# new_v1.net
KiCad netlist of a schematic drawn in EAGLE
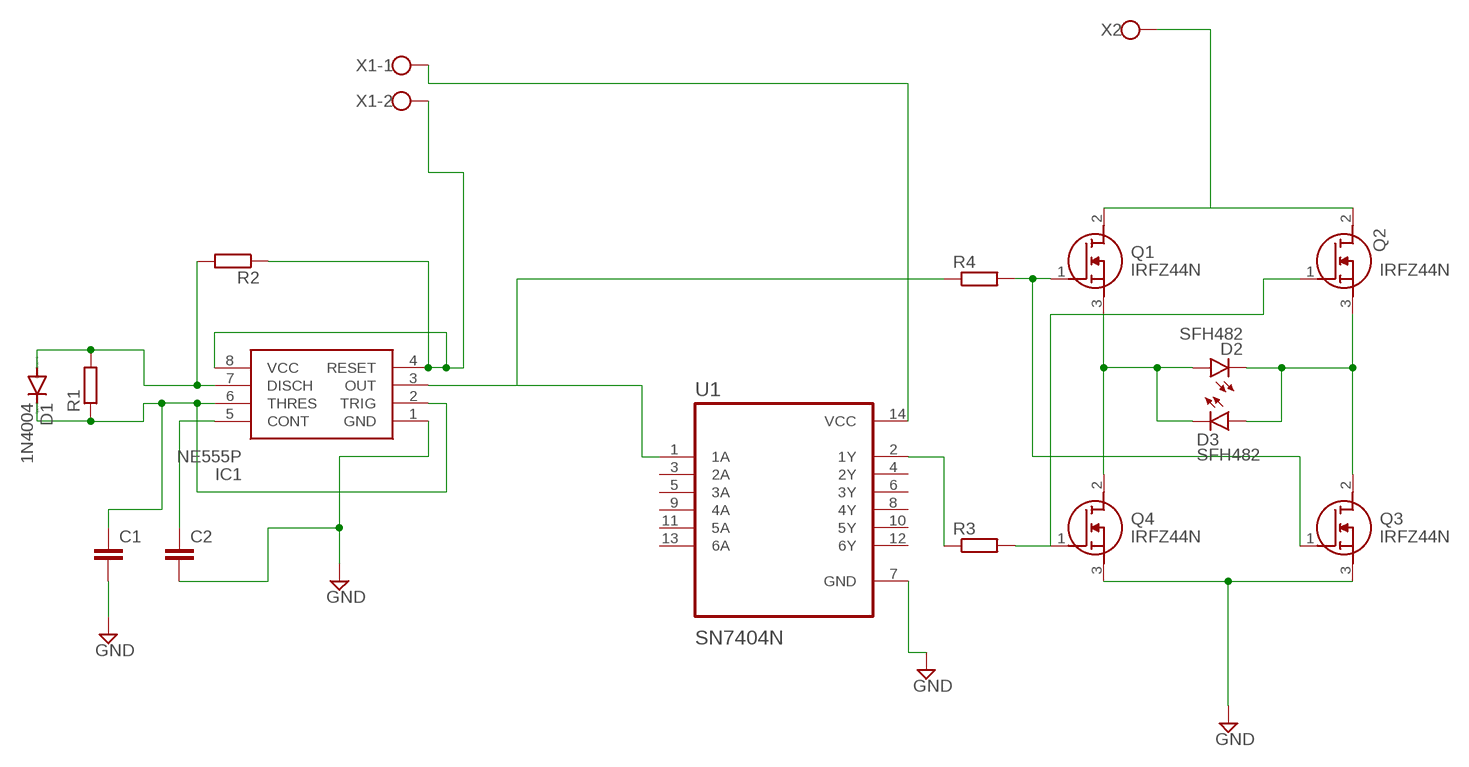
[diagram p0: schematic, sheet 1]

(export (version "E")
  (design (tool "Eeschema 10.0.6"))
  (components
    (comp (ref "C1")
      (value "C-EU025-030X050")
      (footprint "eagle-import:C025-030X050")
      (libsource (lib "eagle-import") (part "C-EU025-030X050"))
    )
    (comp (ref "C2")
      (value "C-EU025-030X050")
      (footprint "eagle-import:C025-030X050")
      (libsource (lib "eagle-import") (part "C-EU025-030X050"))
    )
    (comp (ref "D1")
      (value "1N4004")
      (footprint "eagle-import:DO41-10")
      (libsource (lib "eagle-import") (part "1N4004"))
    )
    (comp (ref "D2")
      (value "SFH482")
      (footprint "eagle-import:SFH482")
      (libsource (lib "eagle-import") (part "SFH482"))
    )
    (comp (ref "D3")
      (value "SFH482")
      (footprint "eagle-import:SFH482")
      (libsource (lib "eagle-import") (part "SFH482"))
    )
    (comp (ref "IC1")
      (value "NE555P")
      (footprint "eagle-import:DIP794W53P254L959H508Q8N")
      (fields (field (name "MOUSER_PART_NUMBER") "595-NE555P"))
      (libsource (lib "eagle-import") (part "NE555P"))
    )
    (comp (ref "Q1")
      (value "IRFZ44N")
      (footprint "eagle-import:TO254P440X1000X1900-3P")
      (libsource (lib "eagle-import") (part "IRFZ44N"))
    )
    (comp (ref "Q2")
      (value "IRFZ44N")
      (footprint "eagle-import:TO254P440X1000X1900-3P")
      (libsource (lib "eagle-import") (part "IRFZ44N"))
    )
    (comp (ref "Q3")
      (value "IRFZ44N")
      (footprint "eagle-import:TO254P440X1000X1900-3P")
      (libsource (lib "eagle-import") (part "IRFZ44N"))
    )
    (comp (ref "Q4")
      (value "IRFZ44N")
      (footprint "eagle-import:TO254P440X1000X1900-3P")
      (libsource (lib "eagle-import") (part "IRFZ44N"))
    )
    (comp (ref "R1")
      (value "R-EU_0207/7")
      (footprint "eagle-import:0207_7")
      (libsource (lib "eagle-import") (part "R-EU_0207/7"))
    )
    (comp (ref "R2")
      (value "R-EU_0207/7")
      (footprint "eagle-import:0207_7")
      (libsource (lib "eagle-import") (part "R-EU_0207/7"))
    )
    (comp (ref "R3")
      (value "R-EU_0207/7")
      (footprint "eagle-import:0207_7")
      (libsource (lib "eagle-import") (part "R-EU_0207/7"))
    )
    (comp (ref "R4")
      (value "R-EU_0207/7")
      (footprint "eagle-import:0207_7")
      (libsource (lib "eagle-import") (part "R-EU_0207/7"))
    )
    (comp (ref "U1")
      (value "SN7404N")
      (footprint "eagle-import:DIP794W45P254L1969H508Q14")
      (fields (field (name "MF") "Texas Instruments"))
      (libsource (lib "eagle-import") (part "SN7404N"))
    )
    (comp (ref "X1")
      (value "W237-102")
      (footprint "eagle-import:W237-102")
      (fields (field (name "MPN") "237-102"))
      (libsource (lib "eagle-import") (part "W237-102"))
    )
    (comp (ref "X2")
      (value "W237-112")
      (footprint "eagle-import:W237-112")
      (fields (field (name "MPN") "237-112"))
      (libsource (lib "eagle-import") (part "W237-112"))
    )
  )
  (nets
    (net (code "1") (name "GND") (class "Default")
      (node (ref "C1") (pin "2") (pinfunction "2_2") (pintype "passive"))
      (node (ref "C2") (pin "2") (pinfunction "2_2") (pintype "passive"))
      (node (ref "IC1") (pin "1") (pinfunction "GND_1") (pintype "bidirectional"))
      (node (ref "Q3") (pin "3") (pinfunction "S_3") (pintype "bidirectional"))
      (node (ref "Q4") (pin "3") (pinfunction "S_3") (pintype "bidirectional"))
      (node (ref "U1") (pin "7") (pinfunction "GND_7") (pintype "power_in"))
    )
    (net (code "2") (name "Net-(D2-C)") (class "Default")
      (node (ref "D2") (pin "K") (pinfunction "C_K") (pintype "passive"))
      (node (ref "D3") (pin "A") (pinfunction "A_A") (pintype "passive"))
      (node (ref "Q2") (pin "3") (pinfunction "S_3") (pintype "bidirectional"))
      (node (ref "Q3") (pin "2") (pinfunction "D_2") (pintype "bidirectional"))
    )
    (net (code "3") (name "Net-(D3-C)") (class "Default")
      (node (ref "D2") (pin "A") (pinfunction "A_A") (pintype "passive"))
      (node (ref "D3") (pin "K") (pinfunction "C_K") (pintype "passive"))
      (node (ref "Q1") (pin "3") (pinfunction "S_3") (pintype "bidirectional"))
      (node (ref "Q4") (pin "2") (pinfunction "D_2") (pintype "bidirectional"))
    )
    (net (code "4") (name "Net-(IC1-CONT)") (class "Default")
      (node (ref "C2") (pin "1") (pinfunction "1_1") (pintype "passive"))
      (node (ref "IC1") (pin "5") (pinfunction "CONT_5") (pintype "bidirectional"))
    )
    (net (code "5") (name "Net-(IC1-DISCH)") (class "Default")
      (node (ref "D1") (pin "A") (pinfunction "A_A") (pintype "passive"))
      (node (ref "IC1") (pin "7") (pinfunction "DISCH_7") (pintype "bidirectional"))
      (node (ref "R1") (pin "2") (pinfunction "2_2") (pintype "passive"))
      (node (ref "R2") (pin "2") (pinfunction "2_2") (pintype "passive"))
    )
    (net (code "6") (name "Net-(IC1-OUT)") (class "Default")
      (node (ref "IC1") (pin "3") (pinfunction "OUT_3") (pintype "bidirectional"))
      (node (ref "R4") (pin "1") (pinfunction "1_1") (pintype "passive"))
      (node (ref "U1") (pin "1") (pinfunction "1A_1") (pintype "input"))
    )
    (net (code "7") (name "Net-(IC1-RESET)") (class "Default")
      (node (ref "IC1") (pin "4") (pinfunction "RESET_4") (pintype "bidirectional"))
      (node (ref "IC1") (pin "8") (pinfunction "VCC_8") (pintype "bidirectional"))
      (node (ref "R2") (pin "1") (pinfunction "1_1") (pintype "passive"))
      (node (ref "X1") (pin "2") (pinfunction "KL_2") (pintype "passive"))
    )
    (net (code "8") (name "Net-(IC1-THRES)") (class "Default")
      (node (ref "C1") (pin "1") (pinfunction "1_1") (pintype "passive"))
      (node (ref "D1") (pin "C") (pinfunction "C_C") (pintype "passive"))
      (node (ref "IC1") (pin "2") (pinfunction "TRIG_2") (pintype "bidirectional"))
      (node (ref "IC1") (pin "6") (pinfunction "THRES_6") (pintype "bidirectional"))
      (node (ref "R1") (pin "1") (pinfunction "1_1") (pintype "passive"))
    )
    (net (code "9") (name "Net-(Q1-D)") (class "Default")
      (node (ref "Q1") (pin "2") (pinfunction "D_2") (pintype "bidirectional"))
      (node (ref "Q2") (pin "2") (pinfunction "D_2") (pintype "bidirectional"))
      (node (ref "X2") (pin "1") (pinfunction "KL_1") (pintype "passive"))
    )
    (net (code "10") (name "Net-(Q1-G)") (class "Default")
      (node (ref "Q1") (pin "1") (pinfunction "G_1") (pintype "bidirectional"))
      (node (ref "Q3") (pin "1") (pinfunction "G_1") (pintype "bidirectional"))
      (node (ref "R4") (pin "2") (pinfunction "2_2") (pintype "passive"))
    )
    (net (code "11") (name "Net-(Q2-G)") (class "Default")
      (node (ref "Q2") (pin "1") (pinfunction "G_1") (pintype "bidirectional"))
      (node (ref "Q4") (pin "1") (pinfunction "G_1") (pintype "bidirectional"))
      (node (ref "R3") (pin "2") (pinfunction "2_2") (pintype "passive"))
    )
    (net (code "12") (name "Net-(U1-1Y)") (class "Default")
      (node (ref "R3") (pin "1") (pinfunction "1_1") (pintype "passive"))
      (node (ref "U1") (pin "2") (pinfunction "1Y_2") (pintype "output"))
    )
    (net (code "13") (name "Net-(U1-VCC)") (class "Default")
      (node (ref "U1") (pin "14") (pinfunction "VCC_14") (pintype "power_in"))
      (node (ref "X1") (pin "1") (pinfunction "KL_1") (pintype "passive"))
    )
    (net (code "14") (name "unconnected-(U1-2A-Pad3)") (class "Default")
      (node (ref "U1") (pin "3") (pinfunction "2A_3") (pintype "input"))
    )
    (net (code "15") (name "unconnected-(U1-2Y-Pad4)") (class "Default")
      (node (ref "U1") (pin "4") (pinfunction "2Y_4") (pintype "output"))
    )
    (net (code "16") (name "unconnected-(U1-3A-Pad5)") (class "Default")
      (node (ref "U1") (pin "5") (pinfunction "3A_5") (pintype "input"))
    )
    (net (code "17") (name "unconnected-(U1-3Y-Pad6)") (class "Default")
      (node (ref "U1") (pin "6") (pinfunction "3Y_6") (pintype "output"))
    )
    (net (code "18") (name "unconnected-(U1-4A-Pad9)") (class "Default")
      (node (ref "U1") (pin "9") (pinfunction "4A_9") (pintype "input"))
    )
    (net (code "19") (name "unconnected-(U1-4Y-Pad8)") (class "Default")
      (node (ref "U1") (pin "8") (pinfunction "4Y_8") (pintype "output"))
    )
    (net (code "20") (name "unconnected-(U1-5A-Pad11)") (class "Default")
      (node (ref "U1") (pin "11") (pinfunction "5A_11") (pintype "input"))
    )
    (net (code "21") (name "unconnected-(U1-5Y-Pad10)") (class "Default")
      (node (ref "U1") (pin "10") (pinfunction "5Y_10") (pintype "output"))
    )
    (net (code "22") (name "unconnected-(U1-6A-Pad13)") (class "Default")
      (node (ref "U1") (pin "13") (pinfunction "6A_13") (pintype "input"))
    )
    (net (code "23") (name "unconnected-(U1-6Y-Pad12)") (class "Default")
      (node (ref "U1") (pin "12") (pinfunction "6Y_12") (pintype "output"))
    )
  )
)
